# mixer1_1st_auto_route.net
KiCad netlist of a schematic drawn in EAGLE
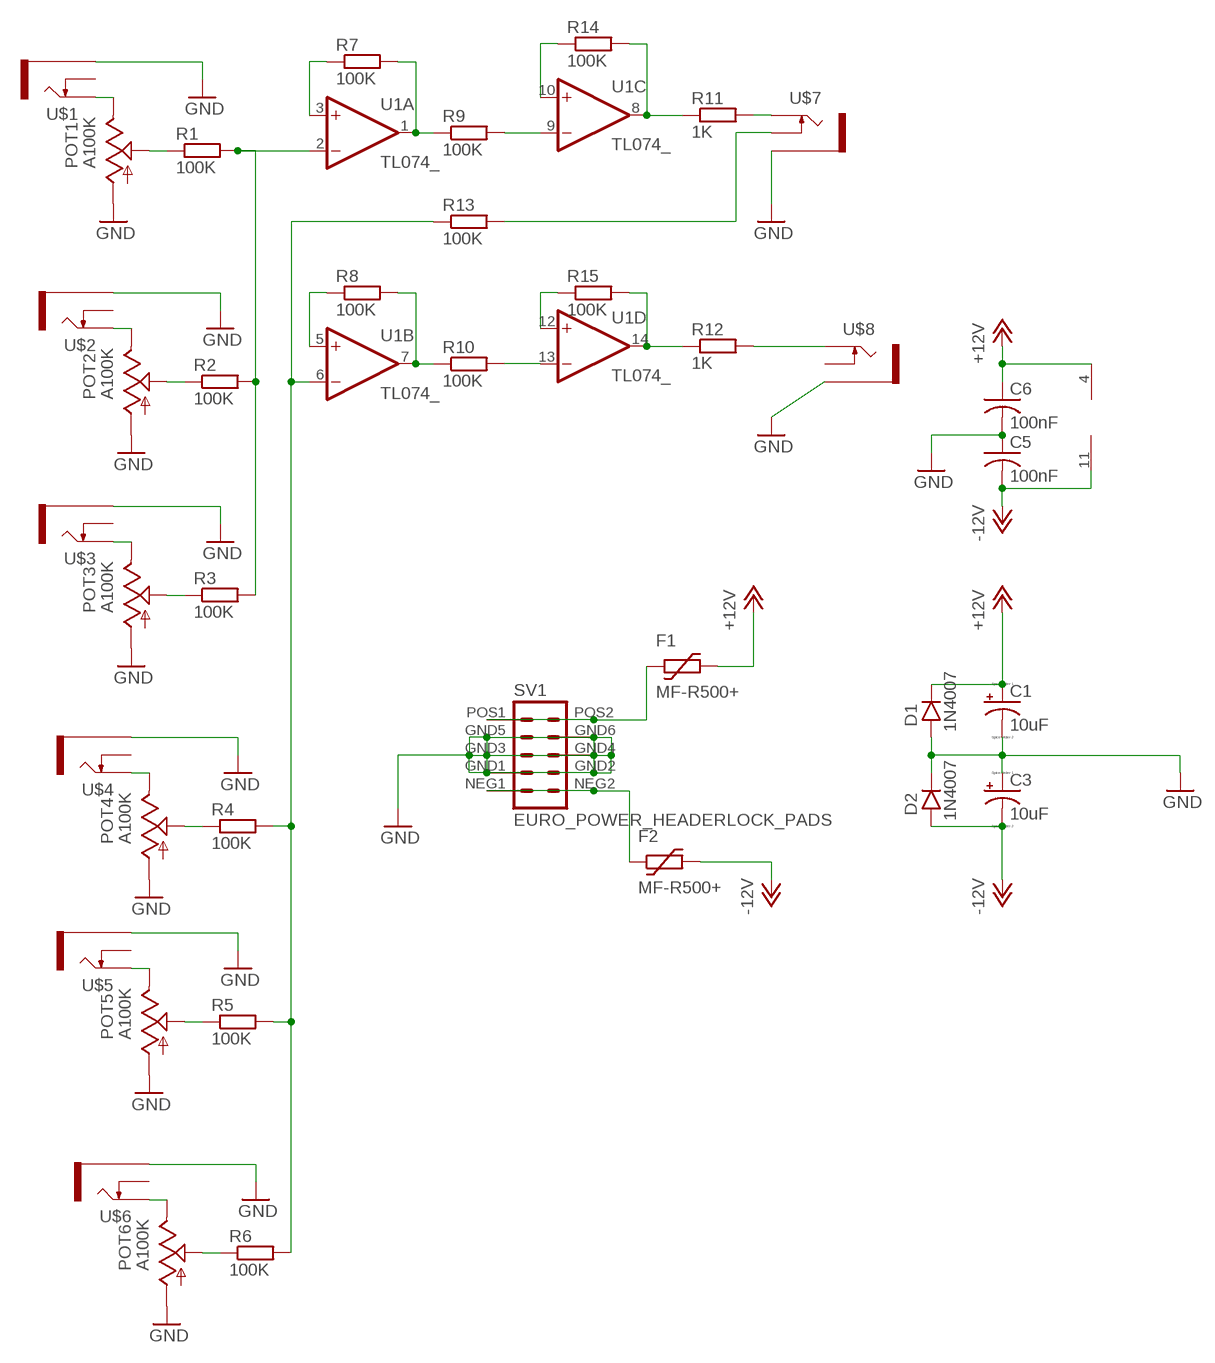
[diagram p0: schematic, sheet 1]

(export (version "E")
  (design (tool "Eeschema 10.0.6"))
  (components
    (comp (ref "C1")
      (value "10uF")
      (footprint "eagle-import:E2,5-7")
      (libsource (lib "eagle-import") (part "CPOL-USE2.5-7"))
    )
    (comp (ref "C3")
      (value "10uF")
      (footprint "eagle-import:E2,5-7")
      (libsource (lib "eagle-import") (part "CPOL-USE2.5-7"))
    )
    (comp (ref "C5")
      (value "100nF")
      (footprint "eagle-import:C075-032X103")
      (libsource (lib "eagle-import") (part "C-US075-032X103"))
    )
    (comp (ref "C6")
      (value "100nF")
      (footprint "eagle-import:C075-032X103")
      (libsource (lib "eagle-import") (part "C-US075-032X103"))
    )
    (comp (ref "D1")
      (value "1N4007")
      (footprint "eagle-import:DO41-3")
      (libsource (lib "eagle-import") (part "1N400X.3"))
    )
    (comp (ref "D2")
      (value "1N4007")
      (footprint "eagle-import:DO41-3")
      (libsource (lib "eagle-import") (part "1N400X.3"))
    )
    (comp (ref "F1")
      (value "MF-R500+")
      (footprint "eagle-import:BOURNS-MF-R")
      (libsource (lib "eagle-import") (part "MF-R500+"))
    )
    (comp (ref "F2")
      (value "MF-R500+")
      (footprint "eagle-import:BOURNS-MF-R")
      (libsource (lib "eagle-import") (part "MF-R500+"))
    )
    (comp (ref "POT1")
      (value "A100K")
      (footprint "eagle-import:9MM_SNAP-IN_POT")
      (libsource (lib "eagle-import") (part "9MM_SNAP-IN_POT_"))
    )
    (comp (ref "POT2")
      (value "A100K")
      (footprint "eagle-import:9MM_SNAP-IN_POT")
      (libsource (lib "eagle-import") (part "9MM_SNAP-IN_POT_"))
    )
    (comp (ref "POT3")
      (value "A100K")
      (footprint "eagle-import:9MM_SNAP-IN_POT")
      (libsource (lib "eagle-import") (part "9MM_SNAP-IN_POT_"))
    )
    (comp (ref "POT4")
      (value "A100K")
      (footprint "eagle-import:9MM_SNAP-IN_POT")
      (libsource (lib "eagle-import") (part "9MM_SNAP-IN_POT_"))
    )
    (comp (ref "POT5")
      (value "A100K")
      (footprint "eagle-import:9MM_SNAP-IN_POT")
      (libsource (lib "eagle-import") (part "9MM_SNAP-IN_POT_"))
    )
    (comp (ref "POT6")
      (value "A100K")
      (footprint "eagle-import:9MM_SNAP-IN_POT")
      (libsource (lib "eagle-import") (part "9MM_SNAP-IN_POT_"))
    )
    (comp (ref "R1")
      (value "100K")
      (footprint "eagle-import:7MM_RESISTOR")
      (libsource (lib "eagle-import") (part "RESISTOR7MM"))
    )
    (comp (ref "R2")
      (value "100K")
      (footprint "eagle-import:7MM_RESISTOR")
      (libsource (lib "eagle-import") (part "RESISTOR7MM"))
    )
    (comp (ref "R3")
      (value "100K")
      (footprint "eagle-import:7MM_RESISTOR")
      (libsource (lib "eagle-import") (part "RESISTOR7MM"))
    )
    (comp (ref "R4")
      (value "100K")
      (footprint "eagle-import:7MM_RESISTOR")
      (libsource (lib "eagle-import") (part "RESISTOR7MM"))
    )
    (comp (ref "R5")
      (value "100K")
      (footprint "eagle-import:7MM_RESISTOR")
      (libsource (lib "eagle-import") (part "RESISTOR7MM"))
    )
    (comp (ref "R6")
      (value "100K")
      (footprint "eagle-import:7MM_RESISTOR")
      (libsource (lib "eagle-import") (part "RESISTOR7MM"))
    )
    (comp (ref "R7")
      (value "100K")
      (footprint "eagle-import:7MM_RESISTOR")
      (libsource (lib "eagle-import") (part "RESISTOR7MM"))
    )
    (comp (ref "R8")
      (value "100K")
      (footprint "eagle-import:7MM_RESISTOR")
      (libsource (lib "eagle-import") (part "RESISTOR7MM"))
    )
    (comp (ref "R9")
      (value "100K")
      (footprint "eagle-import:7MM_RESISTOR")
      (libsource (lib "eagle-import") (part "RESISTOR7MM"))
    )
    (comp (ref "R10")
      (value "100K")
      (footprint "eagle-import:7MM_RESISTOR")
      (libsource (lib "eagle-import") (part "RESISTOR7MM"))
    )
    (comp (ref "R11")
      (value "1K")
      (footprint "eagle-import:7MM_RESISTOR")
      (libsource (lib "eagle-import") (part "RESISTOR7MM"))
    )
    (comp (ref "R12")
      (value "1K")
      (footprint "eagle-import:7MM_RESISTOR")
      (libsource (lib "eagle-import") (part "RESISTOR7MM"))
    )
    (comp (ref "R13")
      (value "100K")
      (footprint "eagle-import:7MM_RESISTOR")
      (libsource (lib "eagle-import") (part "RESISTOR7MM"))
    )
    (comp (ref "R14")
      (value "100K")
      (footprint "eagle-import:7MM_RESISTOR")
      (libsource (lib "eagle-import") (part "RESISTOR7MM"))
    )
    (comp (ref "R15")
      (value "100K")
      (footprint "eagle-import:7MM_RESISTOR")
      (libsource (lib "eagle-import") (part "RESISTOR7MM"))
    )
    (comp (ref "SV1")
      (value "EURO_POWER_HEADERLOCK_PADS")
      (footprint "eagle-import:EURO_PWR_HEADER_LOCK")
      (libsource (lib "eagle-import") (part "EURO_POWER_HEADERLOCK_PADS"))
    )
    (comp (ref "U$1")
      (value "THONKICONNNEW")
      (footprint "eagle-import:WQP-PJ301M-12_JACK")
      (libsource (lib "eagle-import") (part "THONKICONNNEW"))
    )
    (comp (ref "U$2")
      (value "THONKICONNNEW")
      (footprint "eagle-import:WQP-PJ301M-12_JACK")
      (libsource (lib "eagle-import") (part "THONKICONNNEW"))
    )
    (comp (ref "U$3")
      (value "THONKICONNNEW")
      (footprint "eagle-import:WQP-PJ301M-12_JACK")
      (libsource (lib "eagle-import") (part "THONKICONNNEW"))
    )
    (comp (ref "U$4")
      (value "THONKICONNNEW")
      (footprint "eagle-import:WQP-PJ301M-12_JACK")
      (libsource (lib "eagle-import") (part "THONKICONNNEW"))
    )
    (comp (ref "U$5")
      (value "THONKICONNNEW")
      (footprint "eagle-import:WQP-PJ301M-12_JACK")
      (libsource (lib "eagle-import") (part "THONKICONNNEW"))
    )
    (comp (ref "U$6")
      (value "THONKICONNNEW")
      (footprint "eagle-import:WQP-PJ301M-12_JACK")
      (libsource (lib "eagle-import") (part "THONKICONNNEW"))
    )
    (comp (ref "U$7")
      (value "THONKICONNNEW")
      (footprint "eagle-import:WQP-PJ301M-12_JACK")
      (libsource (lib "eagle-import") (part "THONKICONNNEW"))
    )
    (comp (ref "U$8")
      (value "THONKICONNNEW")
      (footprint "eagle-import:WQP-PJ301M-12_JACK")
      (libsource (lib "eagle-import") (part "THONKICONNNEW"))
    )
    (comp (ref "U1")
      (value "TL074_")
      (footprint "eagle-import:DIL14")
      (libsource (lib "eagle-import") (part "TL074_"))
    )
  )
  (nets
    (net (code "1") (name "+12V") (class "Default")
      (node (ref "C1") (pin "+") (pinfunction "+_+") (pintype "passive"))
      (node (ref "C6") (pin "1") (pinfunction "1_1") (pintype "passive"))
      (node (ref "D1") (pin "C") (pinfunction "C_C") (pintype "passive"))
      (node (ref "F1") (pin "P$2") (pinfunction "2_P$2") (pintype "passive"))
      (node (ref "U1") (pin "4") (pinfunction "V+_4") (pintype "power_in"))
    )
    (net (code "2") (name "-12V") (class "Default")
      (node (ref "C3") (pin "-") (pinfunction "-_-") (pintype "passive"))
      (node (ref "C5") (pin "2") (pinfunction "2_2") (pintype "passive"))
      (node (ref "D2") (pin "A") (pinfunction "A_A") (pintype "passive"))
      (node (ref "F2") (pin "P$2") (pinfunction "2_P$2") (pintype "passive"))
      (node (ref "U1") (pin "11") (pinfunction "V-_11") (pintype "power_in"))
    )
    (net (code "3") (name "GND") (class "Default")
      (node (ref "C1") (pin "-") (pinfunction "-_-") (pintype "passive"))
      (node (ref "C3") (pin "+") (pinfunction "+_+") (pintype "passive"))
      (node (ref "C5") (pin "1") (pinfunction "1_1") (pintype "passive"))
      (node (ref "C6") (pin "2") (pinfunction "2_2") (pintype "passive"))
      (node (ref "D1") (pin "A") (pinfunction "A_A") (pintype "passive"))
      (node (ref "D2") (pin "C") (pinfunction "C_C") (pintype "passive"))
      (node (ref "POT1") (pin "1") (pinfunction "A_1") (pintype "passive"))
      (node (ref "POT2") (pin "1") (pinfunction "A_1") (pintype "passive"))
      (node (ref "POT3") (pin "1") (pinfunction "A_1") (pintype "passive"))
      (node (ref "POT4") (pin "1") (pinfunction "A_1") (pintype "passive"))
      (node (ref "POT5") (pin "1") (pinfunction "A_1") (pintype "passive"))
      (node (ref "POT6") (pin "1") (pinfunction "A_1") (pintype "passive"))
      (node (ref "SV1") (pin "GND1") (pinfunction "4_GND1") (pintype "passive"))
      (node (ref "SV1") (pin "GND2") (pinfunction "3_GND2") (pintype "passive"))
      (node (ref "SV1") (pin "GND3") (pinfunction "6_GND3") (pintype "passive"))
      (node (ref "SV1") (pin "GND4") (pinfunction "5_GND4") (pintype "passive"))
      (node (ref "SV1") (pin "GND5") (pinfunction "8_GND5") (pintype "passive"))
      (node (ref "SV1") (pin "GND6") (pinfunction "7_GND6") (pintype "passive"))
      (node (ref "U$1") (pin "P$3_SLEEVE") (pinfunction "SLEEVE_P$3_SLEEVE") (pintype "passive"))
      (node (ref "U$2") (pin "P$3_SLEEVE") (pinfunction "SLEEVE_P$3_SLEEVE") (pintype "passive"))
      (node (ref "U$3") (pin "P$3_SLEEVE") (pinfunction "SLEEVE_P$3_SLEEVE") (pintype "passive"))
      (node (ref "U$4") (pin "P$3_SLEEVE") (pinfunction "SLEEVE_P$3_SLEEVE") (pintype "passive"))
      (node (ref "U$5") (pin "P$3_SLEEVE") (pinfunction "SLEEVE_P$3_SLEEVE") (pintype "passive"))
      (node (ref "U$6") (pin "P$3_SLEEVE") (pinfunction "SLEEVE_P$3_SLEEVE") (pintype "passive"))
      (node (ref "U$7") (pin "P$3_SLEEVE") (pinfunction "SLEEVE_P$3_SLEEVE") (pintype "passive"))
      (node (ref "U$8") (pin "P$3_SLEEVE") (pinfunction "SLEEVE_P$3_SLEEVE") (pintype "passive"))
    )
    (net (code "4") (name "Net-(F1-1)") (class "Default")
      (node (ref "F1") (pin "P$1") (pinfunction "1_P$1") (pintype "passive"))
      (node (ref "SV1") (pin "POS1") (pinfunction "10_POS1") (pintype "passive"))
      (node (ref "SV1") (pin "POS2") (pinfunction "9_POS2") (pintype "passive"))
    )
    (net (code "5") (name "Net-(F2-1)") (class "Default")
      (node (ref "F2") (pin "P$1") (pinfunction "1_P$1") (pintype "passive"))
      (node (ref "SV1") (pin "NEG1") (pinfunction "2_NEG1") (pintype "passive"))
      (node (ref "SV1") (pin "NEG2") (pinfunction "1_NEG2") (pintype "passive"))
    )
    (net (code "6") (name "Net-(POT1-E)") (class "Default")
      (node (ref "POT1") (pin "3") (pinfunction "E_3") (pintype "passive"))
      (node (ref "U$1") (pin "P$1_TIP") (pinfunction "TIP_P$1_TIP") (pintype "passive"))
    )
    (net (code "7") (name "Net-(POT1-S)") (class "Default")
      (node (ref "POT1") (pin "2") (pinfunction "S_2") (pintype "passive"))
      (node (ref "R1") (pin "1") (pinfunction "1_1") (pintype "passive"))
    )
    (net (code "8") (name "Net-(POT2-E)") (class "Default")
      (node (ref "POT2") (pin "3") (pinfunction "E_3") (pintype "passive"))
      (node (ref "U$2") (pin "P$1_TIP") (pinfunction "TIP_P$1_TIP") (pintype "passive"))
    )
    (net (code "9") (name "Net-(POT2-S)") (class "Default")
      (node (ref "POT2") (pin "2") (pinfunction "S_2") (pintype "passive"))
      (node (ref "R2") (pin "1") (pinfunction "1_1") (pintype "passive"))
    )
    (net (code "10") (name "Net-(POT3-E)") (class "Default")
      (node (ref "POT3") (pin "3") (pinfunction "E_3") (pintype "passive"))
      (node (ref "U$3") (pin "P$1_TIP") (pinfunction "TIP_P$1_TIP") (pintype "passive"))
    )
    (net (code "11") (name "Net-(POT3-S)") (class "Default")
      (node (ref "POT3") (pin "2") (pinfunction "S_2") (pintype "passive"))
      (node (ref "R3") (pin "1") (pinfunction "1_1") (pintype "passive"))
    )
    (net (code "12") (name "Net-(POT4-E)") (class "Default")
      (node (ref "POT4") (pin "3") (pinfunction "E_3") (pintype "passive"))
      (node (ref "U$4") (pin "P$1_TIP") (pinfunction "TIP_P$1_TIP") (pintype "passive"))
    )
    (net (code "13") (name "Net-(POT4-S)") (class "Default")
      (node (ref "POT4") (pin "2") (pinfunction "S_2") (pintype "passive"))
      (node (ref "R4") (pin "1") (pinfunction "1_1") (pintype "passive"))
    )
    (net (code "14") (name "Net-(POT5-E)") (class "Default")
      (node (ref "POT5") (pin "3") (pinfunction "E_3") (pintype "passive"))
      (node (ref "U$5") (pin "P$1_TIP") (pinfunction "TIP_P$1_TIP") (pintype "passive"))
    )
    (net (code "15") (name "Net-(POT5-S)") (class "Default")
      (node (ref "POT5") (pin "2") (pinfunction "S_2") (pintype "passive"))
      (node (ref "R5") (pin "1") (pinfunction "1_1") (pintype "passive"))
    )
    (net (code "16") (name "Net-(POT6-E)") (class "Default")
      (node (ref "POT6") (pin "3") (pinfunction "E_3") (pintype "passive"))
      (node (ref "U$6") (pin "P$1_TIP") (pinfunction "TIP_P$1_TIP") (pintype "passive"))
    )
    (net (code "17") (name "Net-(POT6-S)") (class "Default")
      (node (ref "POT6") (pin "2") (pinfunction "S_2") (pintype "passive"))
      (node (ref "R6") (pin "1") (pinfunction "1_1") (pintype "passive"))
    )
    (net (code "18") (name "Net-(U$7-SWITCH)") (class "Default")
      (node (ref "R13") (pin "2") (pinfunction "2_2") (pintype "passive"))
      (node (ref "U$7") (pin "P$2_SWITCH") (pinfunction "SWITCH_P$2_SWITCH") (pintype "passive"))
    )
    (net (code "19") (name "Net-(U$7-TIP)") (class "Default")
      (node (ref "R11") (pin "2") (pinfunction "2_2") (pintype "passive"))
      (node (ref "U$7") (pin "P$1_TIP") (pinfunction "TIP_P$1_TIP") (pintype "passive"))
    )
    (net (code "20") (name "Net-(U$8-TIP)") (class "Default")
      (node (ref "R12") (pin "2") (pinfunction "2_2") (pintype "passive"))
      (node (ref "U$8") (pin "P$1_TIP") (pinfunction "TIP_P$1_TIP") (pintype "passive"))
    )
    (net (code "21") (name "Net-(U1A-+IN)") (class "Default")
      (node (ref "R7") (pin "1") (pinfunction "1_1") (pintype "passive"))
      (node (ref "U1") (pin "3") (pinfunction "+IN_3") (pintype "input"))
    )
    (net (code "22") (name "Net-(U1A--IN)") (class "Default")
      (node (ref "R1") (pin "2") (pinfunction "2_2") (pintype "passive"))
      (node (ref "R2") (pin "2") (pinfunction "2_2") (pintype "passive"))
      (node (ref "R3") (pin "2") (pinfunction "2_2") (pintype "passive"))
      (node (ref "U1") (pin "2") (pinfunction "-IN_2") (pintype "input"))
    )
    (net (code "23") (name "Net-(U1A-OUT)") (class "Default")
      (node (ref "R7") (pin "2") (pinfunction "2_2") (pintype "passive"))
      (node (ref "R9") (pin "1") (pinfunction "1_1") (pintype "passive"))
      (node (ref "U1") (pin "1") (pinfunction "OUT_1") (pintype "output"))
    )
    (net (code "24") (name "Net-(U1B-+IN)") (class "Default")
      (node (ref "R8") (pin "1") (pinfunction "1_1") (pintype "passive"))
      (node (ref "U1") (pin "5") (pinfunction "+IN_5") (pintype "input"))
    )
    (net (code "25") (name "Net-(U1B--IN)") (class "Default")
      (node (ref "R13") (pin "1") (pinfunction "1_1") (pintype "passive"))
      (node (ref "R4") (pin "2") (pinfunction "2_2") (pintype "passive"))
      (node (ref "R5") (pin "2") (pinfunction "2_2") (pintype "passive"))
      (node (ref "R6") (pin "2") (pinfunction "2_2") (pintype "passive"))
      (node (ref "U1") (pin "6") (pinfunction "-IN_6") (pintype "input"))
    )
    (net (code "26") (name "Net-(U1B-OUT)") (class "Default")
      (node (ref "R10") (pin "1") (pinfunction "1_1") (pintype "passive"))
      (node (ref "R8") (pin "2") (pinfunction "2_2") (pintype "passive"))
      (node (ref "U1") (pin "7") (pinfunction "OUT_7") (pintype "output"))
    )
    (net (code "27") (name "Net-(U1C-+IN)") (class "Default")
      (node (ref "R14") (pin "1") (pinfunction "1_1") (pintype "passive"))
      (node (ref "U1") (pin "10") (pinfunction "+IN_10") (pintype "input"))
    )
    (net (code "28") (name "Net-(U1C--IN)") (class "Default")
      (node (ref "R9") (pin "2") (pinfunction "2_2") (pintype "passive"))
      (node (ref "U1") (pin "9") (pinfunction "-IN_9") (pintype "input"))
    )
    (net (code "29") (name "Net-(U1C-OUT)") (class "Default")
      (node (ref "R11") (pin "1") (pinfunction "1_1") (pintype "passive"))
      (node (ref "R14") (pin "2") (pinfunction "2_2") (pintype "passive"))
      (node (ref "U1") (pin "8") (pinfunction "OUT_8") (pintype "output"))
    )
    (net (code "30") (name "Net-(U1D-+IN)") (class "Default")
      (node (ref "R15") (pin "1") (pinfunction "1_1") (pintype "passive"))
      (node (ref "U1") (pin "12") (pinfunction "+IN_12") (pintype "input"))
    )
    (net (code "31") (name "Net-(U1D--IN)") (class "Default")
      (node (ref "R10") (pin "2") (pinfunction "2_2") (pintype "passive"))
      (node (ref "U1") (pin "13") (pinfunction "-IN_13") (pintype "input"))
    )
    (net (code "32") (name "Net-(U1D-OUT)") (class "Default")
      (node (ref "R12") (pin "1") (pinfunction "1_1") (pintype "passive"))
      (node (ref "R15") (pin "2") (pinfunction "2_2") (pintype "passive"))
      (node (ref "U1") (pin "14") (pinfunction "OUT_14") (pintype "output"))
    )
    (net (code "33") (name "unconnected-(U$1-SWITCH-PadP$2_SWITCH)") (class "Default")
      (node (ref "U$1") (pin "P$2_SWITCH") (pinfunction "SWITCH_P$2_SWITCH") (pintype "passive"))
    )
    (net (code "34") (name "unconnected-(U$2-SWITCH-PadP$2_SWITCH)") (class "Default")
      (node (ref "U$2") (pin "P$2_SWITCH") (pinfunction "SWITCH_P$2_SWITCH") (pintype "passive"))
    )
    (net (code "35") (name "unconnected-(U$3-SWITCH-PadP$2_SWITCH)") (class "Default")
      (node (ref "U$3") (pin "P$2_SWITCH") (pinfunction "SWITCH_P$2_SWITCH") (pintype "passive"))
    )
    (net (code "36") (name "unconnected-(U$4-SWITCH-PadP$2_SWITCH)") (class "Default")
      (node (ref "U$4") (pin "P$2_SWITCH") (pinfunction "SWITCH_P$2_SWITCH") (pintype "passive"))
    )
    (net (code "37") (name "unconnected-(U$5-SWITCH-PadP$2_SWITCH)") (class "Default")
      (node (ref "U$5") (pin "P$2_SWITCH") (pinfunction "SWITCH_P$2_SWITCH") (pintype "passive"))
    )
    (net (code "38") (name "unconnected-(U$6-SWITCH-PadP$2_SWITCH)") (class "Default")
      (node (ref "U$6") (pin "P$2_SWITCH") (pinfunction "SWITCH_P$2_SWITCH") (pintype "passive"))
    )
    (net (code "39") (name "unconnected-(U$8-SWITCH-PadP$2_SWITCH)") (class "Default")
      (node (ref "U$8") (pin "P$2_SWITCH") (pinfunction "SWITCH_P$2_SWITCH") (pintype "passive"))
    )
  )
)
